# 01-POWER.net
KiCad netlist of a schematic drawn in Altium Designer
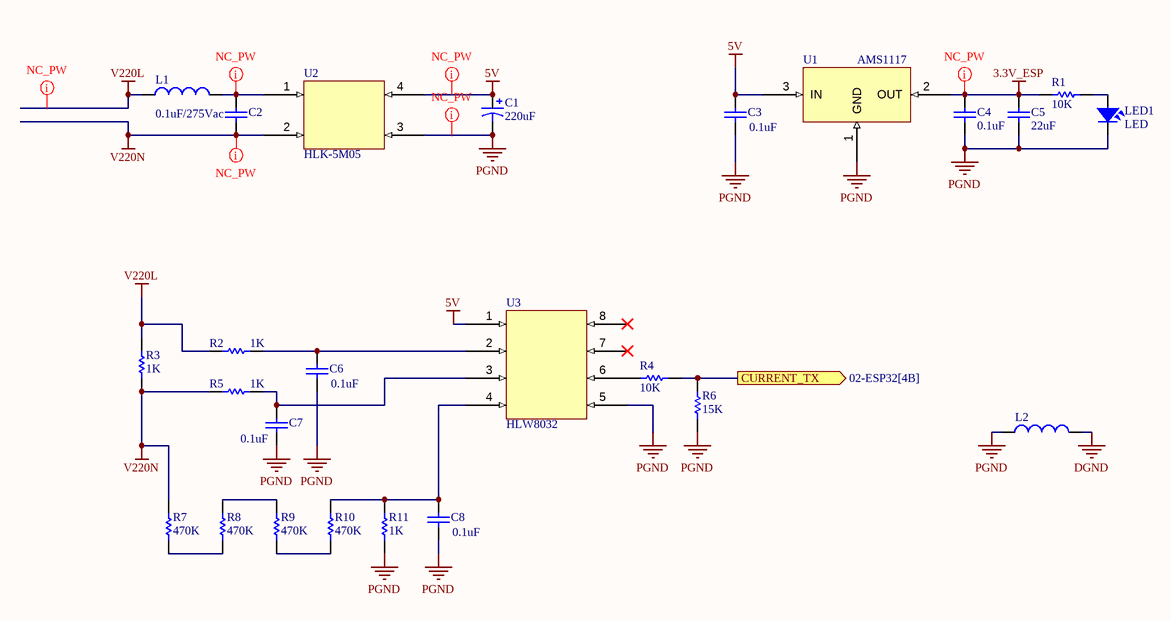
[diagram p0: 01-POWER.SchDoc]

(export (version "E")
  (design (tool "Eeschema 10.0.6"))
  (components
    (comp (ref "C1")
      (value "220uF")
      (footprint "CAP ALU CASE G SMD")
      (description "CAP ALU 220UF 20% 50V SMD")
      (fields
        (field (name "MANUFACTURER") "Nichicon")
        (field (name "MANUFACTURER PART NUMBER") "UPW1J331MHD")
      )
      (libsource (lib "GSHT_181013") (part "330uF/50V/ALU12.5X20mm/20%/7000Hrs"))
    )
    (comp (ref "C2")
      (value "0.1uF/275Vac")
      (footprint "CN2")
      (fields (field (name "MANUFACTURER") "Murata"))
      (libsource (lib "GSHT_181013") (part "0.1uF/50V/C0603/10%"))
    )
    (comp (ref "C3")
      (value "0.1uF")
      (footprint "CAP_CERA_C2012(CC0805INCH)")
      (description "0.1µF ±10% 25V Ceramic Capacitor X7R 0805 (2012 Metric)")
      (libsource (lib "GSHT_181013") (part "0.1uF/50V/C0603/10%"))
    )
    (comp (ref "C4")
      (value "0.1uF")
      (footprint "CAP_CERA_C2012(CC0805INCH)")
      (description "0.1µF ±10% 25V Ceramic Capacitor X7R 0805 (2012 Metric)")
      (libsource (lib "GSHT_181013") (part "0.1uF/50V/C0603/10%"))
    )
    (comp (ref "C5")
      (value "22uF")
      (footprint "CAP TANT CASE A SMD")
      (description "22µF ±20% 25V Ceramic Capacitor X5R 0805 (2012 Metric)")
      (fields (field (name "MANUFACTURER") "Tariff Applied"))
      (libsource (lib "GSHT_181013") (part "0.1uF/50V/C0603/10%"))
    )
    (comp (ref "C6")
      (value "0.1uF")
      (footprint "Cap Ceramic 0603 SMD")
      (description "CAP CER 0.1UF 50V 10% X7R 0603")
      (fields
        (field (name "MANUFACTURER") "Murata Electronics North America")
        (field (name "MANUFACTURER PART NUMBER") "GRM188R71H104KA93D")
      )
      (libsource (lib "GSHT_181013") (part "0.1uF/50V/C0603/10%"))
    )
    (comp (ref "C7")
      (value "0.1uF")
      (footprint "Cap Ceramic 0603 SMD")
      (description "CAP CER 0.1UF 50V 10% X7R 0603")
      (fields
        (field (name "MANUFACTURER") "Murata Electronics North America")
        (field (name "MANUFACTURER PART NUMBER") "GRM188R71H104KA93D")
      )
      (libsource (lib "GSHT_181013") (part "0.1uF/50V/C0603/10%"))
    )
    (comp (ref "C8")
      (value "0.1uF")
      (footprint "Cap Ceramic 0603 SMD")
      (description "CAP CER 0.1UF 50V 10% X7R 0603")
      (fields
        (field (name "MANUFACTURER") "Murata Electronics North America")
        (field (name "MANUFACTURER PART NUMBER") "GRM188R71H104KA93D")
      )
      (libsource (lib "GSHT_181013") (part "0.1uF/50V/C0603/10%"))
    )
    (comp (ref "L1")
      (value "ASPI-7318-8R2M-TCT-ND")
      (footprint "FUSE2_5A")
      (description "Sensible value10-15mH，current\r\n70-500mA")
      (libsource (lib "lpson") (part "Inductor"))
    )
    (comp (ref "L2")
      (value "ASPI-7318-8R2M-TCT-ND")
      (footprint "RES-ERJ3G-1608MM")
      (description "Sensible value10-15mH，current\r\n70-500mA")
      (libsource (lib "lpson") (part "Inductor"))
    )
    (comp (ref "LED1")
      (value "LED")
      (footprint "LED5R")
      (description "LED Single colour Green and Red")
      (libsource (lib "lpson") (part "LED"))
    )
    (comp (ref "R1")
      (value "10K")
      (footprint "Res 0603 SMD")
      (description "RES SMD 10K OHM 1% 1/10W 0603")
      (fields
        (field (name "MANUFACTURER") "Yageo")
        (field (name "MANUFACTURER PART NUMBER") "RC0603FR-0715KL")
      )
      (libsource (lib "GSHT_181013") (part "15K/R0603/1%"))
    )
    (comp (ref "R2")
      (value "1K")
      (footprint "Res 0603 SMD")
      (description "RES SMD 1K OHM 1% 1/10W 0603")
      (fields
        (field (name "MANUFACTURER") "Yageo")
        (field (name "MANUFACTURER PART NUMBER") "RC0603FR-0715KL")
      )
      (libsource (lib "GSHT_181013") (part "15K/R0603/1%"))
    )
    (comp (ref "R3")
      (value "1K")
      (footprint "CFR25S")
      (description "RES SMD 1K OHM 1% 1/10W 0603")
      (fields
        (field (name "MANUFACTURER") "Yageo")
        (field (name "MANUFACTURER PART NUMBER") "RC0603FR-0715KL")
      )
      (libsource (lib "GSHT_181013") (part "15K/R0603/1%"))
    )
    (comp (ref "R4")
      (value "10K")
      (footprint "Res 0603 SMD")
      (description "RES SMD 10K OHM 1% 1/10W 0603")
      (fields
        (field (name "MANUFACTURER") "Yageo")
        (field (name "MANUFACTURER PART NUMBER") "RC0603FR-0715KL")
      )
      (libsource (lib "GSHT_181013") (part "15K/R0603/1%"))
    )
    (comp (ref "R5")
      (value "1K")
      (footprint "Res 0603 SMD")
      (description "RES SMD 1K OHM 1% 1/10W 0603")
      (fields
        (field (name "MANUFACTURER") "Yageo")
        (field (name "MANUFACTURER PART NUMBER") "RC0603FR-0715KL")
      )
      (libsource (lib "GSHT_181013") (part "15K/R0603/1%"))
    )
    (comp (ref "R6")
      (value "15K")
      (footprint "Res 0603 SMD")
      (description "RES SMD 15K OHM 1% 1/10W 0603")
      (fields
        (field (name "MANUFACTURER") "Yageo")
        (field (name "MANUFACTURER PART NUMBER") "RC0603FR-0715KL")
      )
      (libsource (lib "GSHT_181013") (part "15K/R0603/1%"))
    )
    (comp (ref "R7")
      (value "470K")
      (footprint "Res 0603 SMD")
      (description "RES SMD 470K OHM 1% 1/10W 0603")
      (fields
        (field (name "MANUFACTURER") "Yageo")
        (field (name "MANUFACTURER PART NUMBER") "RC0603FR-0715KL")
      )
      (libsource (lib "GSHT_181013") (part "15K/R0603/1%"))
    )
    (comp (ref "R8")
      (value "470K")
      (footprint "Res 0603 SMD")
      (description "RES SMD 470K OHM 1% 1/10W 0603")
      (fields
        (field (name "MANUFACTURER") "Yageo")
        (field (name "MANUFACTURER PART NUMBER") "RC0603FR-0715KL")
      )
      (libsource (lib "GSHT_181013") (part "15K/R0603/1%"))
    )
    (comp (ref "R9")
      (value "470K")
      (footprint "Res 0603 SMD")
      (description "RES SMD 470K OHM 1% 1/10W 0603")
      (fields
        (field (name "MANUFACTURER") "Yageo")
        (field (name "MANUFACTURER PART NUMBER") "RC0603FR-0715KL")
      )
      (libsource (lib "GSHT_181013") (part "15K/R0603/1%"))
    )
    (comp (ref "R10")
      (value "470K")
      (footprint "Res 0603 SMD")
      (description "RES SMD 470K OHM 1% 1/10W 0603")
      (fields
        (field (name "MANUFACTURER") "Yageo")
        (field (name "MANUFACTURER PART NUMBER") "RC0603FR-0715KL")
      )
      (libsource (lib "GSHT_181013") (part "15K/R0603/1%"))
    )
    (comp (ref "R11")
      (value "1K")
      (footprint "Res 0603 SMD")
      (description "RES SMD 1K OHM 1% 1/10W 0603")
      (fields
        (field (name "MANUFACTURER") "Yageo")
        (field (name "MANUFACTURER PART NUMBER") "RC0603FR-0715KL")
      )
      (libsource (lib "GSHT_181013") (part "15K/R0603/1%"))
    )
    (comp (ref "U1")
      (value "AMS1117")
      (footprint "AMS1117-3.3V")
      (libsource (lib "Schlib1") (part "AMS1117"))
    )
    (comp (ref "U2")
      (value "HLK-5M05")
      (footprint "HILINK 5V/3W")
      (libsource (lib "Schlib1") (part "HLK-5M05"))
    )
    (comp (ref "U3") (value "HLW8032") (footprint "SO-8") (libsource (lib "Schlib1") (part "HLW8032")))
  )
  (nets
    (net (code "1") (name "/CURRENT_TX") (class "Default")
      (node (ref "R4") (pin "2") (pinfunction "2_2") (pintype "passive"))
      (node (ref "R6") (pin "1") (pinfunction "1_1") (pintype "passive"))
    )
    (net (code "2") (name "3.3V_ESP") (class "Default")
      (node (ref "C4") (pin "2") (pinfunction "2_2") (pintype "passive"))
      (node (ref "C5") (pin "2") (pinfunction "2_2") (pintype "passive"))
      (node (ref "R1") (pin "1") (pinfunction "1_1") (pintype "passive"))
      (node (ref "U1") (pin "2") (pinfunction "OUT_2") (pintype "input"))
    )
    (net (code "3") (name "5V") (class "Default")
      (node (ref "C1") (pin "1") (pinfunction "1_1") (pintype "passive"))
      (node (ref "C3") (pin "2") (pinfunction "2_2") (pintype "passive"))
      (node (ref "U1") (pin "3") (pinfunction "IN_3") (pintype "input"))
      (node (ref "U2") (pin "4") (pintype "input"))
      (node (ref "U3") (pin "1") (pintype "input"))
    )
    (net (code "4") (name "DGND") (class "Default")
      (node (ref "L2") (pin "2") (pinfunction "2_2") (pintype "passive"))
    )
    (net (code "5") (name "Net-(C2-Pad2)") (class "Default")
      (node (ref "C2") (pin "2") (pinfunction "2_2") (pintype "passive"))
      (node (ref "L1") (pin "2") (pinfunction "2_2") (pintype "passive"))
      (node (ref "U2") (pin "1") (pintype "input"))
    )
    (net (code "6") (name "Net-(C6-Pad2)") (class "Default")
      (node (ref "C6") (pin "2") (pinfunction "2_2") (pintype "passive"))
      (node (ref "R2") (pin "1") (pinfunction "1_1") (pintype "passive"))
      (node (ref "U3") (pin "2") (pintype "input"))
    )
    (net (code "7") (name "Net-(C7-Pad2)") (class "Default")
      (node (ref "C7") (pin "2") (pinfunction "2_2") (pintype "passive"))
      (node (ref "R5") (pin "1") (pinfunction "1_1") (pintype "passive"))
      (node (ref "U3") (pin "3") (pintype "input"))
    )
    (net (code "8") (name "Net-(C8-Pad2)") (class "Default")
      (node (ref "C8") (pin "2") (pinfunction "2_2") (pintype "passive"))
      (node (ref "R10") (pin "1") (pinfunction "1_1") (pintype "passive"))
      (node (ref "R11") (pin "2") (pinfunction "2_2") (pintype "passive"))
      (node (ref "U3") (pin "4") (pintype "input"))
    )
    (net (code "9") (name "Net-(LED1-Pad1)") (class "Default")
      (node (ref "LED1") (pin "1") (pinfunction "1_1") (pintype "passive"))
      (node (ref "R1") (pin "2") (pinfunction "2_2") (pintype "passive"))
    )
    (net (code "10") (name "Net-(R4-Pad1)") (class "Default")
      (node (ref "R4") (pin "1") (pinfunction "1_1") (pintype "passive"))
      (node (ref "U3") (pin "6") (pintype "input"))
    )
    (net (code "11") (name "Net-(R7-Pad2)") (class "Default")
      (node (ref "R7") (pin "2") (pinfunction "2_2") (pintype "passive"))
      (node (ref "R8") (pin "2") (pinfunction "2_2") (pintype "passive"))
    )
    (net (code "12") (name "Net-(R8-Pad1)") (class "Default")
      (node (ref "R8") (pin "1") (pinfunction "1_1") (pintype "passive"))
      (node (ref "R9") (pin "1") (pinfunction "1_1") (pintype "passive"))
    )
    (net (code "13") (name "Net-(R10-Pad2)") (class "Default")
      (node (ref "R10") (pin "2") (pinfunction "2_2") (pintype "passive"))
      (node (ref "R9") (pin "2") (pinfunction "2_2") (pintype "passive"))
    )
    (net (code "14") (name "PGND") (class "Default")
      (node (ref "C1") (pin "2") (pinfunction "2_2") (pintype "passive"))
      (node (ref "C3") (pin "1") (pinfunction "1_1") (pintype "passive"))
      (node (ref "C4") (pin "1") (pinfunction "1_1") (pintype "passive"))
      (node (ref "C5") (pin "1") (pinfunction "1_1") (pintype "passive"))
      (node (ref "C6") (pin "1") (pinfunction "1_1") (pintype "passive"))
      (node (ref "C7") (pin "1") (pinfunction "1_1") (pintype "passive"))
      (node (ref "C8") (pin "1") (pinfunction "1_1") (pintype "passive"))
      (node (ref "L2") (pin "1") (pinfunction "1_1") (pintype "passive"))
      (node (ref "LED1") (pin "2") (pinfunction "2_2") (pintype "passive"))
      (node (ref "R11") (pin "1") (pinfunction "1_1") (pintype "passive"))
      (node (ref "R6") (pin "2") (pinfunction "2_2") (pintype "passive"))
      (node (ref "U1") (pin "1") (pinfunction "GND_1") (pintype "input"))
      (node (ref "U2") (pin "3") (pintype "input"))
      (node (ref "U3") (pin "5") (pintype "input"))
    )
    (net (code "15") (name "V220L") (class "Default")
      (node (ref "L1") (pin "1") (pinfunction "1_1") (pintype "passive"))
      (node (ref "R2") (pin "2") (pinfunction "2_2") (pintype "passive"))
      (node (ref "R3") (pin "1") (pinfunction "1_1") (pintype "passive"))
    )
    (net (code "16") (name "V220N") (class "Default")
      (node (ref "C2") (pin "1") (pinfunction "1_1") (pintype "passive"))
      (node (ref "R3") (pin "2") (pinfunction "2_2") (pintype "passive"))
      (node (ref "R5") (pin "2") (pinfunction "2_2") (pintype "passive"))
      (node (ref "R7") (pin "1") (pinfunction "1_1") (pintype "passive"))
      (node (ref "U2") (pin "2") (pintype "input"))
    )
    (net (code "17") (name "unconnected-(U3-Pad7)") (class "Default")
      (node (ref "U3") (pin "7") (pintype "input+no_connect"))
    )
    (net (code "18") (name "unconnected-(U3-Pad8)") (class "Default")
      (node (ref "U3") (pin "8") (pintype "input+no_connect"))
    )
  )
)
